# Flash.net
KiCad netlist of a schematic drawn in Altium Designer
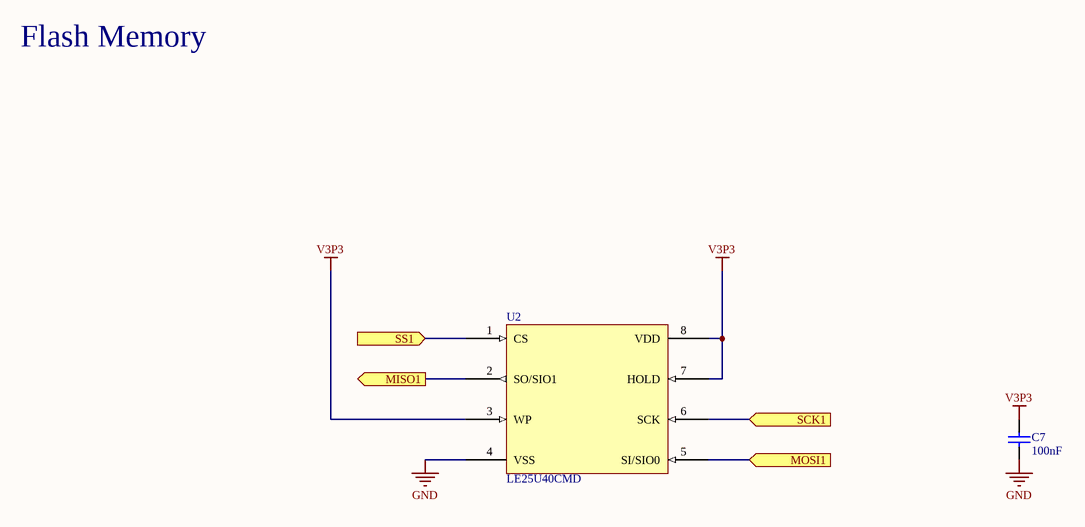
[diagram p0: Flash.SchDoc]

(export (version "E")
  (design (tool "Eeschema 10.0.6"))
  (components
    (comp (ref "C7")
      (value "100nF")
      (footprint "own_0603")
      (description "Capacitor")
      (fields (field (name "PUBLISHER") "Altium Limited"))
      (libsource (lib "Miscellaneous Devices") (part "Cap"))
    )
    (comp (ref "U2")
      (value "LE25U40CMD")
      (footprint "LE25U40CMDTWG")
      (description "Flash memory")
      (libsource (lib "Schlib") (part "LE25U40CMD"))
    )
  )
  (nets
    (net (code "1") (name "/MISO1") (class "Default")
      (node (ref "U2") (pin "2") (pinfunction "SO/SIO1_2") (pintype "output"))
    )
    (net (code "2") (name "/MOSI1") (class "Default")
      (node (ref "U2") (pin "5") (pinfunction "SI/SIO0_5") (pintype "input"))
    )
    (net (code "3") (name "/SCK1") (class "Default")
      (node (ref "U2") (pin "6") (pinfunction "SCK_6") (pintype "input"))
    )
    (net (code "4") (name "/SS1") (class "Default")
      (node (ref "U2") (pin "1") (pinfunction "CS_1") (pintype "input"))
    )
    (net (code "5") (name "GND") (class "Default")
      (node (ref "C7") (pin "1") (pinfunction "1_1") (pintype "passive"))
      (node (ref "U2") (pin "4") (pinfunction "VSS_4") (pintype "power_in"))
    )
    (net (code "6") (name "V3P3") (class "Default")
      (node (ref "C7") (pin "2") (pinfunction "2_2") (pintype "passive"))
      (node (ref "U2") (pin "3") (pinfunction "WP_3") (pintype "input"))
      (node (ref "U2") (pin "7") (pinfunction "HOLD_7") (pintype "input"))
      (node (ref "U2") (pin "8") (pinfunction "VDD_8") (pintype "power_in"))
    )
  )
)
